# SFP.net
KiCad netlist of a schematic drawn in Altium Designer
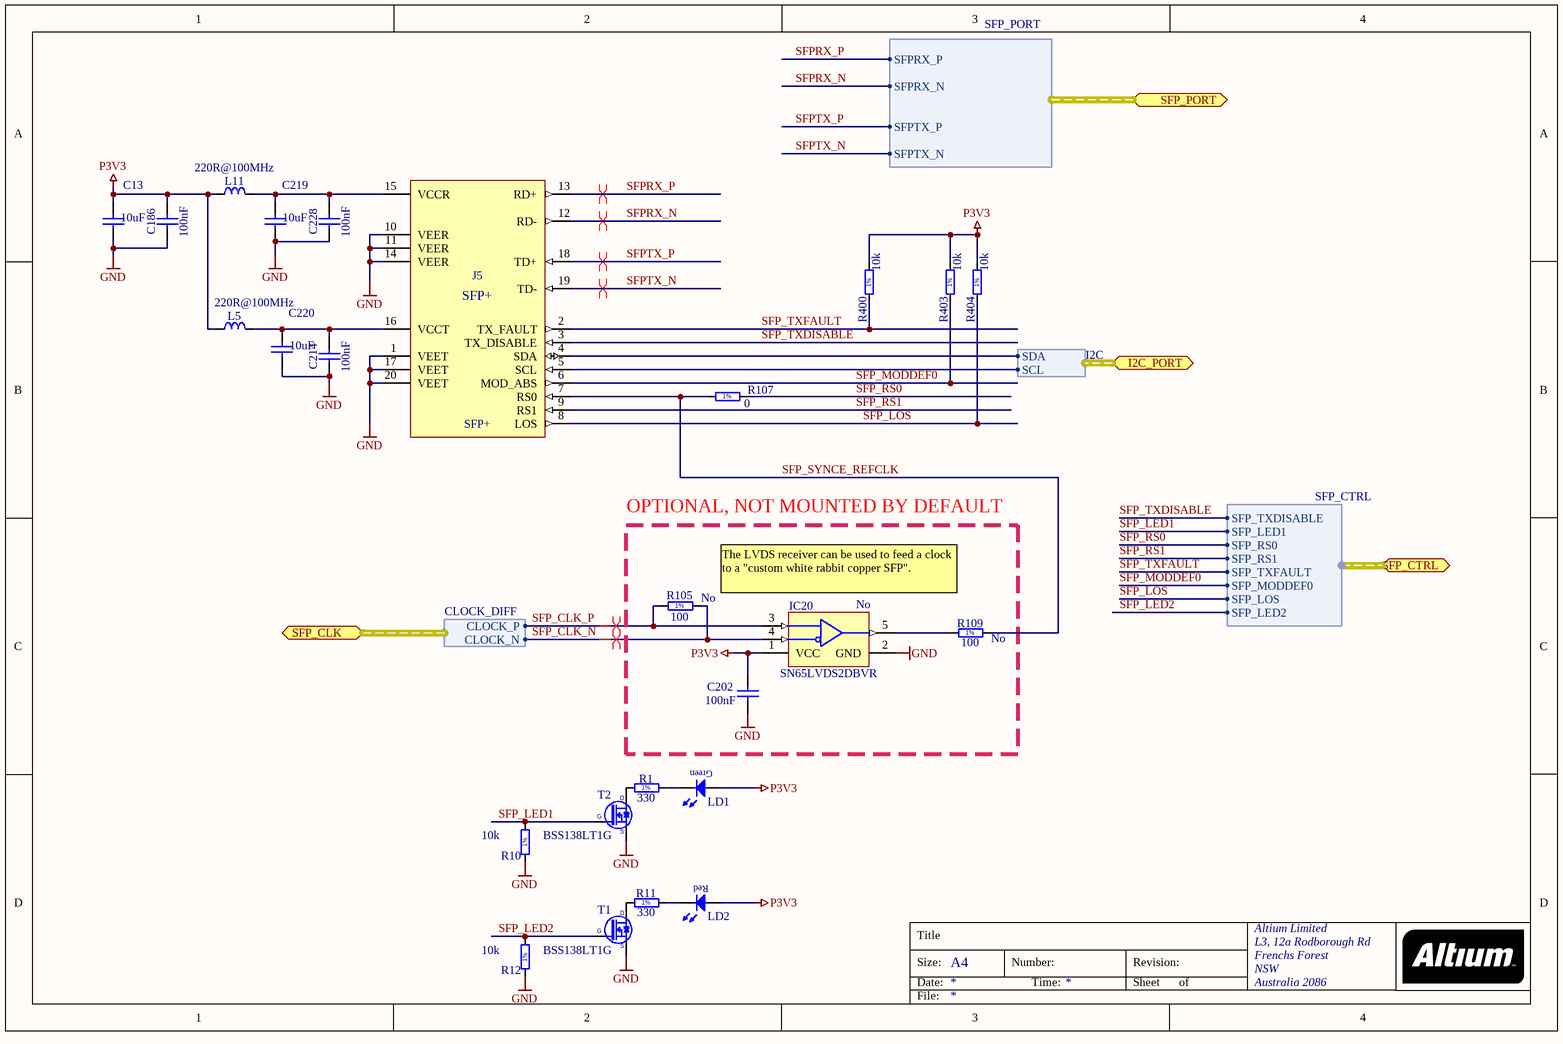
[diagram p0: SFP.SchDoc]

(export (version "E")
  (design (tool "Eeschema 10.0.6"))
  (components
    (comp (ref "C13")
      (value "10uF")
      (footprint "CAPC2012X135N")
      (description "Non-polarised capacitor")
      (fields
        (field (name "PART NUMBER") "CC0805_10UF_10V_10%_X7R")
        (field (name "VOLTAGE") "10V")
        (field (name "AUTHOR") "CERN DEM JLC")
      )
      (libsource (lib "Capacitors") (part "Capacitor - non polarized"))
    )
    (comp (ref "C186")
      (value "100nF")
      (footprint "CAPC1005X55N")
      (description "Non-polarised capacitor")
      (fields
        (field (name "PART NUMBER") "CC0402_100NF_16V_10%_X7R")
        (field (name "VOLTAGE") "16V")
        (field (name "AUTHOR") "CERN DEM JLC")
      )
      (libsource (lib "Capacitors") (part "Capacitor - non polarized"))
    )
    (comp (ref "C202")
      (value "100nF")
      (footprint "CAPC1005X55N")
      (description "Non-polarised capacitor")
      (fields
        (field (name "PART NUMBER") "CC0402_100NF_16V_10%_X7R")
        (field (name "VOLTAGE") "16V")
        (field (name "AUTHOR") "CERN DEM JLC")
      )
      (libsource (lib "Capacitors") (part "Capacitor - non polarized"))
    )
    (comp (ref "C214")
      (value "100nF")
      (footprint "CAPC1005X55N")
      (description "Non-polarised capacitor")
      (fields
        (field (name "PART NUMBER") "CC0402_100NF_16V_10%_X7R")
        (field (name "VOLTAGE") "16V")
        (field (name "AUTHOR") "CERN DEM JLC")
      )
      (libsource (lib "Capacitors") (part "Capacitor - non polarized"))
    )
    (comp (ref "C219")
      (value "10uF")
      (footprint "CAPC2012X135N")
      (description "Non-polarised capacitor")
      (fields
        (field (name "PART NUMBER") "CC0805_10UF_10V_10%_X7R")
        (field (name "VOLTAGE") "10V")
        (field (name "AUTHOR") "CERN DEM JLC")
      )
      (libsource (lib "Capacitors") (part "Capacitor - non polarized"))
    )
    (comp (ref "C220")
      (value "10uF")
      (footprint "CAPC2012X135N")
      (description "Non-polarised capacitor")
      (fields
        (field (name "PART NUMBER") "CC0805_10UF_10V_10%_X7R")
        (field (name "VOLTAGE") "10V")
        (field (name "AUTHOR") "CERN DEM JLC")
      )
      (libsource (lib "Capacitors") (part "Capacitor - non polarized"))
    )
    (comp (ref "C228")
      (value "100nF")
      (footprint "CAPC1005X55N")
      (description "Non-polarised capacitor")
      (fields
        (field (name "PART NUMBER") "CC0402_100NF_16V_10%_X7R")
        (field (name "VOLTAGE") "16V")
        (field (name "AUTHOR") "CERN DEM JLC")
      )
      (libsource (lib "Capacitors") (part "Capacitor - non polarized"))
    )
    (comp (ref "IC20")
      (value "SN65LVDS2DBVR")
      (footprint "SOT95P280X145-5N")
      (description "High-Speed Differential Line Receiver")
      (fields
        (field (name "MANUFACTURER") "TEXAS INSTRUMENTS")
        (field (name "MOUNTED") "No")
        (field (name "AUTHOR") "CERN DEM JLC")
      )
      (libsource (lib "ICs And Semiconductors") (part "SN65LVDS2DBVR"))
    )
    (comp (ref "J5")
      (value "SFP+")
      (footprint "TYCO_1888247-1")
      (description "20 Position SFP+ Connector (Small Form-factor Pluggable)")
      (fields
        (field (name "PART NUMBER") "TYCO_1888247-1")
        (field (name "MANUFACTURER") "TYCO ELECTRONICS")
        (field (name "AUTHOR") "CERN DEM JLC")
      )
      (libsource (lib "Connectors") (part "SFP+x1"))
    )
    (comp (ref "L5")
      (value "220R@100MHz")
      (footprint "INDC2012X105N")
      (description "Inductor")
      (fields
        (field (name "PART NUMBER") "IND0805_MURATA_BLM21PG221SN1D")
        (field (name "POWER") "2A")
        (field (name "AUTHOR") "CERN DEM JLC")
      )
      (libsource (lib "Inductors & Transformers") (part "Inductor"))
    )
    (comp (ref "L11")
      (value "220R@100MHz")
      (footprint "INDC2012X105N")
      (description "Inductor")
      (fields
        (field (name "PART NUMBER") "IND0805_MURATA_BLM21PG221SN1D")
        (field (name "POWER") "2A")
        (field (name "AUTHOR") "CERN DEM JLC")
      )
      (libsource (lib "Inductors & Transformers") (part "Inductor"))
    )
    (comp (ref "LD1")
      (value "Green")
      (footprint "LED_AVAGO_HSME-C120")
      (description "LED Green 1C 2A")
      (fields
        (field (name "PART NUMBER") "LED_AVAGO_HSME-C120")
        (field (name "MANUFACTURER") "AVAGO TECHNOLOGIES")
        (field (name "AUTHOR") "CERN DEM JMW")
      )
      (libsource (lib "ICs And Semiconductors") (part "LED Green 1C 2A"))
    )
    (comp (ref "LD2")
      (value "Red")
      (footprint "LED_AVAGO_HSMC-C120")
      (description "LED Red 1C 2A")
      (fields
        (field (name "PART NUMBER") "LED_AVAGO_HSMC-C120")
        (field (name "MANUFACTURER") "AVAGO TECHNOLOGIES")
        (field (name "AUTHOR") "CERN DEM JMW")
      )
      (libsource (lib "ICs And Semiconductors") (part "LED Red 1C 2A"))
    )
    (comp (ref "R1")
      (value "330")
      (footprint "RESC1608X55N")
      (description "Resistor - 1%")
      (fields
        (field (name "PART NUMBER") "R0603_330R_1%_0.1W_100PPM")
        (field (name "POWER") "0.1W")
        (field (name "AUTHOR") "CERN DEM JLC")
      )
      (libsource (lib "Resistors") (part "Resistor - 1%"))
    )
    (comp (ref "R10")
      (value "10k")
      (footprint "RESC1608X55N")
      (description "Resistor - 1%")
      (fields
        (field (name "PART NUMBER") "R0603_10K_1%_0.1W_100PPM")
        (field (name "POWER") "0.1W")
        (field (name "AUTHOR") "CERN DEM JLC")
      )
      (libsource (lib "Resistors") (part "Resistor - 1%"))
    )
    (comp (ref "R11")
      (value "330")
      (footprint "RESC1608X55N")
      (description "Resistor - 1%")
      (fields
        (field (name "PART NUMBER") "R0603_330R_1%_0.1W_100PPM")
        (field (name "POWER") "0.1W")
        (field (name "AUTHOR") "CERN DEM JLC")
      )
      (libsource (lib "Resistors") (part "Resistor - 1%"))
    )
    (comp (ref "R12")
      (value "10k")
      (footprint "RESC1608X55N")
      (description "Resistor - 1%")
      (fields
        (field (name "PART NUMBER") "R0603_10K_1%_0.1W_100PPM")
        (field (name "POWER") "0.1W")
        (field (name "AUTHOR") "CERN DEM JLC")
      )
      (libsource (lib "Resistors") (part "Resistor - 1%"))
    )
    (comp (ref "R105")
      (value "100")
      (footprint "RESC1608X55N")
      (description "Resistor - 1%")
      (fields
        (field (name "PART NUMBER") "R0603_100R_1%_0.1W_100PPM")
        (field (name "POWER") "0.1W")
        (field (name "MOUNTED") "No")
        (field (name "AUTHOR") "CERN DEM JLC")
      )
      (libsource (lib "Resistors") (part "Resistor - 1%"))
    )
    (comp (ref "R107")
      (value "0")
      (footprint "RESC1608X55N")
      (description "Resistor - 1%")
      (fields
        (field (name "PART NUMBER") "R0603_0R_JUMPER")
        (field (name "MANUFACTURER") "GENERIC")
        (field (name "AUTHOR") "CERN DEM JLC")
      )
      (libsource (lib "Resistors") (part "Resistor - 1%"))
    )
    (comp (ref "R109")
      (value "100")
      (footprint "RESC1608X55N")
      (description "Resistor - 1%")
      (fields
        (field (name "PART NUMBER") "R0603_100R_1%_0.1W_100PPM")
        (field (name "POWER") "0.1W")
        (field (name "MOUNTED") "No")
        (field (name "AUTHOR") "CERN DEM JLC")
      )
      (libsource (lib "Resistors") (part "Resistor - 1%"))
    )
    (comp (ref "R400")
      (value "10k")
      (footprint "RESC1608X55N")
      (description "Resistor - 1%")
      (fields
        (field (name "PART NUMBER") "R0603_10K_1%_0.1W_100PPM")
        (field (name "POWER") "0.1W")
        (field (name "AUTHOR") "CERN DEM JLC")
      )
      (libsource (lib "Resistors") (part "Resistor - 1%"))
    )
    (comp (ref "R403")
      (value "10k")
      (footprint "RESC1608X55N")
      (description "Resistor - 1%")
      (fields
        (field (name "PART NUMBER") "R0603_10K_1%_0.1W_100PPM")
        (field (name "POWER") "0.1W")
        (field (name "AUTHOR") "CERN DEM JLC")
      )
      (libsource (lib "Resistors") (part "Resistor - 1%"))
    )
    (comp (ref "R404")
      (value "10k")
      (footprint "RESC1608X55N")
      (description "Resistor - 1%")
      (fields
        (field (name "PART NUMBER") "R0603_10K_1%_0.1W_100PPM")
        (field (name "POWER") "0.1W")
        (field (name "AUTHOR") "CERN DEM JLC")
      )
      (libsource (lib "Resistors") (part "Resistor - 1%"))
    )
    (comp (ref "T1")
      (value "BSS138LT1G")
      (footprint "SOT95P240X110-3N")
      (description "N-CHANNEL MOSFET WITH DIODE")
      (fields (field (name "MANUFACTURER") "ON SEMICONDUCTOR") (field (name "AUTHOR") "CERN DEM JLC"))
      (libsource (lib "ICs And Semiconductors") (part "N-MOSFET-D 1G 2S 3D"))
    )
    (comp (ref "T2")
      (value "BSS138LT1G")
      (footprint "SOT95P240X110-3N")
      (description "N-CHANNEL MOSFET WITH DIODE")
      (fields (field (name "MANUFACTURER") "ON SEMICONDUCTOR") (field (name "AUTHOR") "CERN DEM JLC"))
      (libsource (lib "ICs And Semiconductors") (part "N-MOSFET-D 1G 2S 3D"))
    )
  )
  (nets
    (net (code "5") (name "/SCL") (class "Default")
      (node (ref "J5") (pin "5") (pinfunction "SCL_5") (pintype "input"))
    )
    (net (code "6") (name "/SDA") (class "Default")
      (node (ref "J5") (pin "4") (pinfunction "SDA_4") (pintype "bidirectional"))
    )
    (net (code "7") (name "/SFPRX_N") (class "Default")
      (node (ref "J5") (pin "12") (pinfunction "RD-_12") (pintype "output"))
    )
    (net (code "8") (name "/SFPRX_P") (class "Default")
      (node (ref "J5") (pin "13") (pinfunction "RD+_13") (pintype "output"))
    )
    (net (code "9") (name "/SFPTX_N") (class "Default")
      (node (ref "J5") (pin "19") (pinfunction "TD-_19") (pintype "input"))
    )
    (net (code "10") (name "/SFPTX_P") (class "Default")
      (node (ref "J5") (pin "18") (pinfunction "TD+_18") (pintype "input"))
    )
    (net (code "11") (name "/SFP_CLK_N") (class "Default")
      (node (ref "IC20") (pin "4") (pinfunction "B_4") (pintype "input"))
      (node (ref "R105") (pin "2") (pinfunction "2_2") (pintype "passive"))
    )
    (net (code "12") (name "/SFP_CLK_P") (class "Default")
      (node (ref "IC20") (pin "3") (pinfunction "A_3") (pintype "input"))
      (node (ref "R105") (pin "1") (pinfunction "1_1") (pintype "passive"))
    )
    (net (code "13") (name "/SFP_LED1") (class "Default")
      (node (ref "R10") (pin "2") (pinfunction "2_2") (pintype "passive"))
      (node (ref "T2") (pin "1") (pinfunction "G_1") (pintype "passive"))
    )
    (net (code "14") (name "/SFP_LED2") (class "Default")
      (node (ref "R12") (pin "2") (pinfunction "2_2") (pintype "passive"))
      (node (ref "T1") (pin "1") (pinfunction "G_1") (pintype "passive"))
    )
    (net (code "15") (name "/SFP_LOS") (class "Default")
      (node (ref "J5") (pin "8") (pinfunction "LOS_8") (pintype "output"))
      (node (ref "R404") (pin "1") (pinfunction "1_1") (pintype "passive"))
    )
    (net (code "16") (name "/SFP_MODDEF0") (class "Default")
      (node (ref "J5") (pin "6") (pinfunction "MOD_ABS_6") (pintype "output"))
      (node (ref "R403") (pin "1") (pinfunction "1_1") (pintype "passive"))
    )
    (net (code "17") (name "/SFP_RS0") (class "Default")
      (node (ref "R107") (pin "2") (pinfunction "2_2") (pintype "passive"))
    )
    (net (code "18") (name "/SFP_RS1") (class "Default")
      (node (ref "J5") (pin "9") (pinfunction "RS1_9") (pintype "input"))
    )
    (net (code "19") (name "/SFP_SYNCE_REFCLK") (class "Default")
      (node (ref "J5") (pin "7") (pinfunction "RS0_7") (pintype "input"))
      (node (ref "R107") (pin "1") (pinfunction "1_1") (pintype "passive"))
      (node (ref "R109") (pin "2") (pinfunction "2_2") (pintype "passive"))
    )
    (net (code "20") (name "/SFP_TXDISABLE") (class "Default")
      (node (ref "J5") (pin "3") (pinfunction "TX_DISABLE_3") (pintype "input"))
    )
    (net (code "21") (name "/SFP_TXFAULT") (class "Default")
      (node (ref "J5") (pin "2") (pinfunction "TX_FAULT_2") (pintype "output"))
      (node (ref "R400") (pin "1") (pinfunction "1_1") (pintype "passive"))
    )
    (net (code "26") (name "GND") (class "Default")
      (node (ref "C13") (pin "2") (pinfunction "2_2") (pintype "passive"))
      (node (ref "C186") (pin "2") (pinfunction "2_2") (pintype "passive"))
      (node (ref "C202") (pin "1") (pinfunction "1_1") (pintype "passive"))
      (node (ref "C214") (pin "2") (pinfunction "2_2") (pintype "passive"))
      (node (ref "C219") (pin "2") (pinfunction "2_2") (pintype "passive"))
      (node (ref "C220") (pin "2") (pinfunction "2_2") (pintype "passive"))
      (node (ref "C228") (pin "2") (pinfunction "2_2") (pintype "passive"))
      (node (ref "IC20") (pin "2") (pinfunction "GND_2") (pintype "power_in"))
      (node (ref "J5") (pin "1") (pinfunction "VEET_1") (pintype "power_in"))
      (node (ref "J5") (pin "10") (pinfunction "VEER_10") (pintype "power_in"))
      (node (ref "J5") (pin "11") (pinfunction "VEER_11") (pintype "power_in"))
      (node (ref "J5") (pin "14") (pinfunction "VEER_14") (pintype "power_in"))
      (node (ref "J5") (pin "17") (pinfunction "VEET_17") (pintype "power_in"))
      (node (ref "J5") (pin "20") (pinfunction "VEET_20") (pintype "power_in"))
      (node (ref "R10") (pin "1") (pinfunction "1_1") (pintype "passive"))
      (node (ref "R12") (pin "1") (pinfunction "1_1") (pintype "passive"))
      (node (ref "T1") (pin "2") (pinfunction "S_2") (pintype "passive"))
      (node (ref "T2") (pin "2") (pinfunction "S_2") (pintype "passive"))
    )
    (net (code "27") (name "Net-(IC20-R)") (class "Default")
      (node (ref "IC20") (pin "5") (pinfunction "R_5") (pintype "output"))
      (node (ref "R109") (pin "1") (pinfunction "1_1") (pintype "passive"))
    )
    (net (code "28") (name "Net-(J5-VCCR)") (class "Default")
      (node (ref "C219") (pin "1") (pinfunction "1_1") (pintype "passive"))
      (node (ref "C228") (pin "1") (pinfunction "1_1") (pintype "passive"))
      (node (ref "J5") (pin "15") (pinfunction "VCCR_15") (pintype "power_in"))
      (node (ref "L11") (pin "2") (pinfunction "2_2") (pintype "passive"))
    )
    (net (code "29") (name "Net-(J5-VCCT)") (class "Default")
      (node (ref "C214") (pin "1") (pinfunction "1_1") (pintype "passive"))
      (node (ref "C220") (pin "1") (pinfunction "1_1") (pintype "passive"))
      (node (ref "J5") (pin "16") (pinfunction "VCCT_16") (pintype "power_in"))
      (node (ref "L5") (pin "2") (pinfunction "2_2") (pintype "passive"))
    )
    (net (code "30") (name "Net-(LD1-C)") (class "Default")
      (node (ref "LD1") (pin "1") (pinfunction "C_1") (pintype "passive"))
      (node (ref "R1") (pin "2") (pinfunction "2_2") (pintype "passive"))
    )
    (net (code "31") (name "Net-(LD2-C)") (class "Default")
      (node (ref "LD2") (pin "1") (pinfunction "C_1") (pintype "passive"))
      (node (ref "R11") (pin "2") (pinfunction "2_2") (pintype "passive"))
    )
    (net (code "32") (name "Net-(T1-D)") (class "Default")
      (node (ref "R11") (pin "1") (pinfunction "1_1") (pintype "passive"))
      (node (ref "T1") (pin "3") (pinfunction "D_3") (pintype "passive"))
    )
    (net (code "33") (name "Net-(T2-D)") (class "Default")
      (node (ref "R1") (pin "1") (pinfunction "1_1") (pintype "passive"))
      (node (ref "T2") (pin "3") (pinfunction "D_3") (pintype "passive"))
    )
    (net (code "34") (name "P3V3") (class "Default")
      (node (ref "C13") (pin "1") (pinfunction "1_1") (pintype "passive"))
      (node (ref "C186") (pin "1") (pinfunction "1_1") (pintype "passive"))
      (node (ref "C202") (pin "2") (pinfunction "2_2") (pintype "passive"))
      (node (ref "IC20") (pin "1") (pinfunction "VCC_1") (pintype "power_in"))
      (node (ref "L11") (pin "1") (pinfunction "1_1") (pintype "passive"))
      (node (ref "L5") (pin "1") (pinfunction "1_1") (pintype "passive"))
      (node (ref "LD1") (pin "2") (pinfunction "A_2") (pintype "passive"))
      (node (ref "LD2") (pin "2") (pinfunction "A_2") (pintype "passive"))
      (node (ref "R400") (pin "2") (pinfunction "2_2") (pintype "passive"))
      (node (ref "R403") (pin "2") (pinfunction "2_2") (pintype "passive"))
      (node (ref "R404") (pin "2") (pinfunction "2_2") (pintype "passive"))
    )
  )
)
